# MCU.net
KiCad netlist of a schematic drawn in Altium Designer
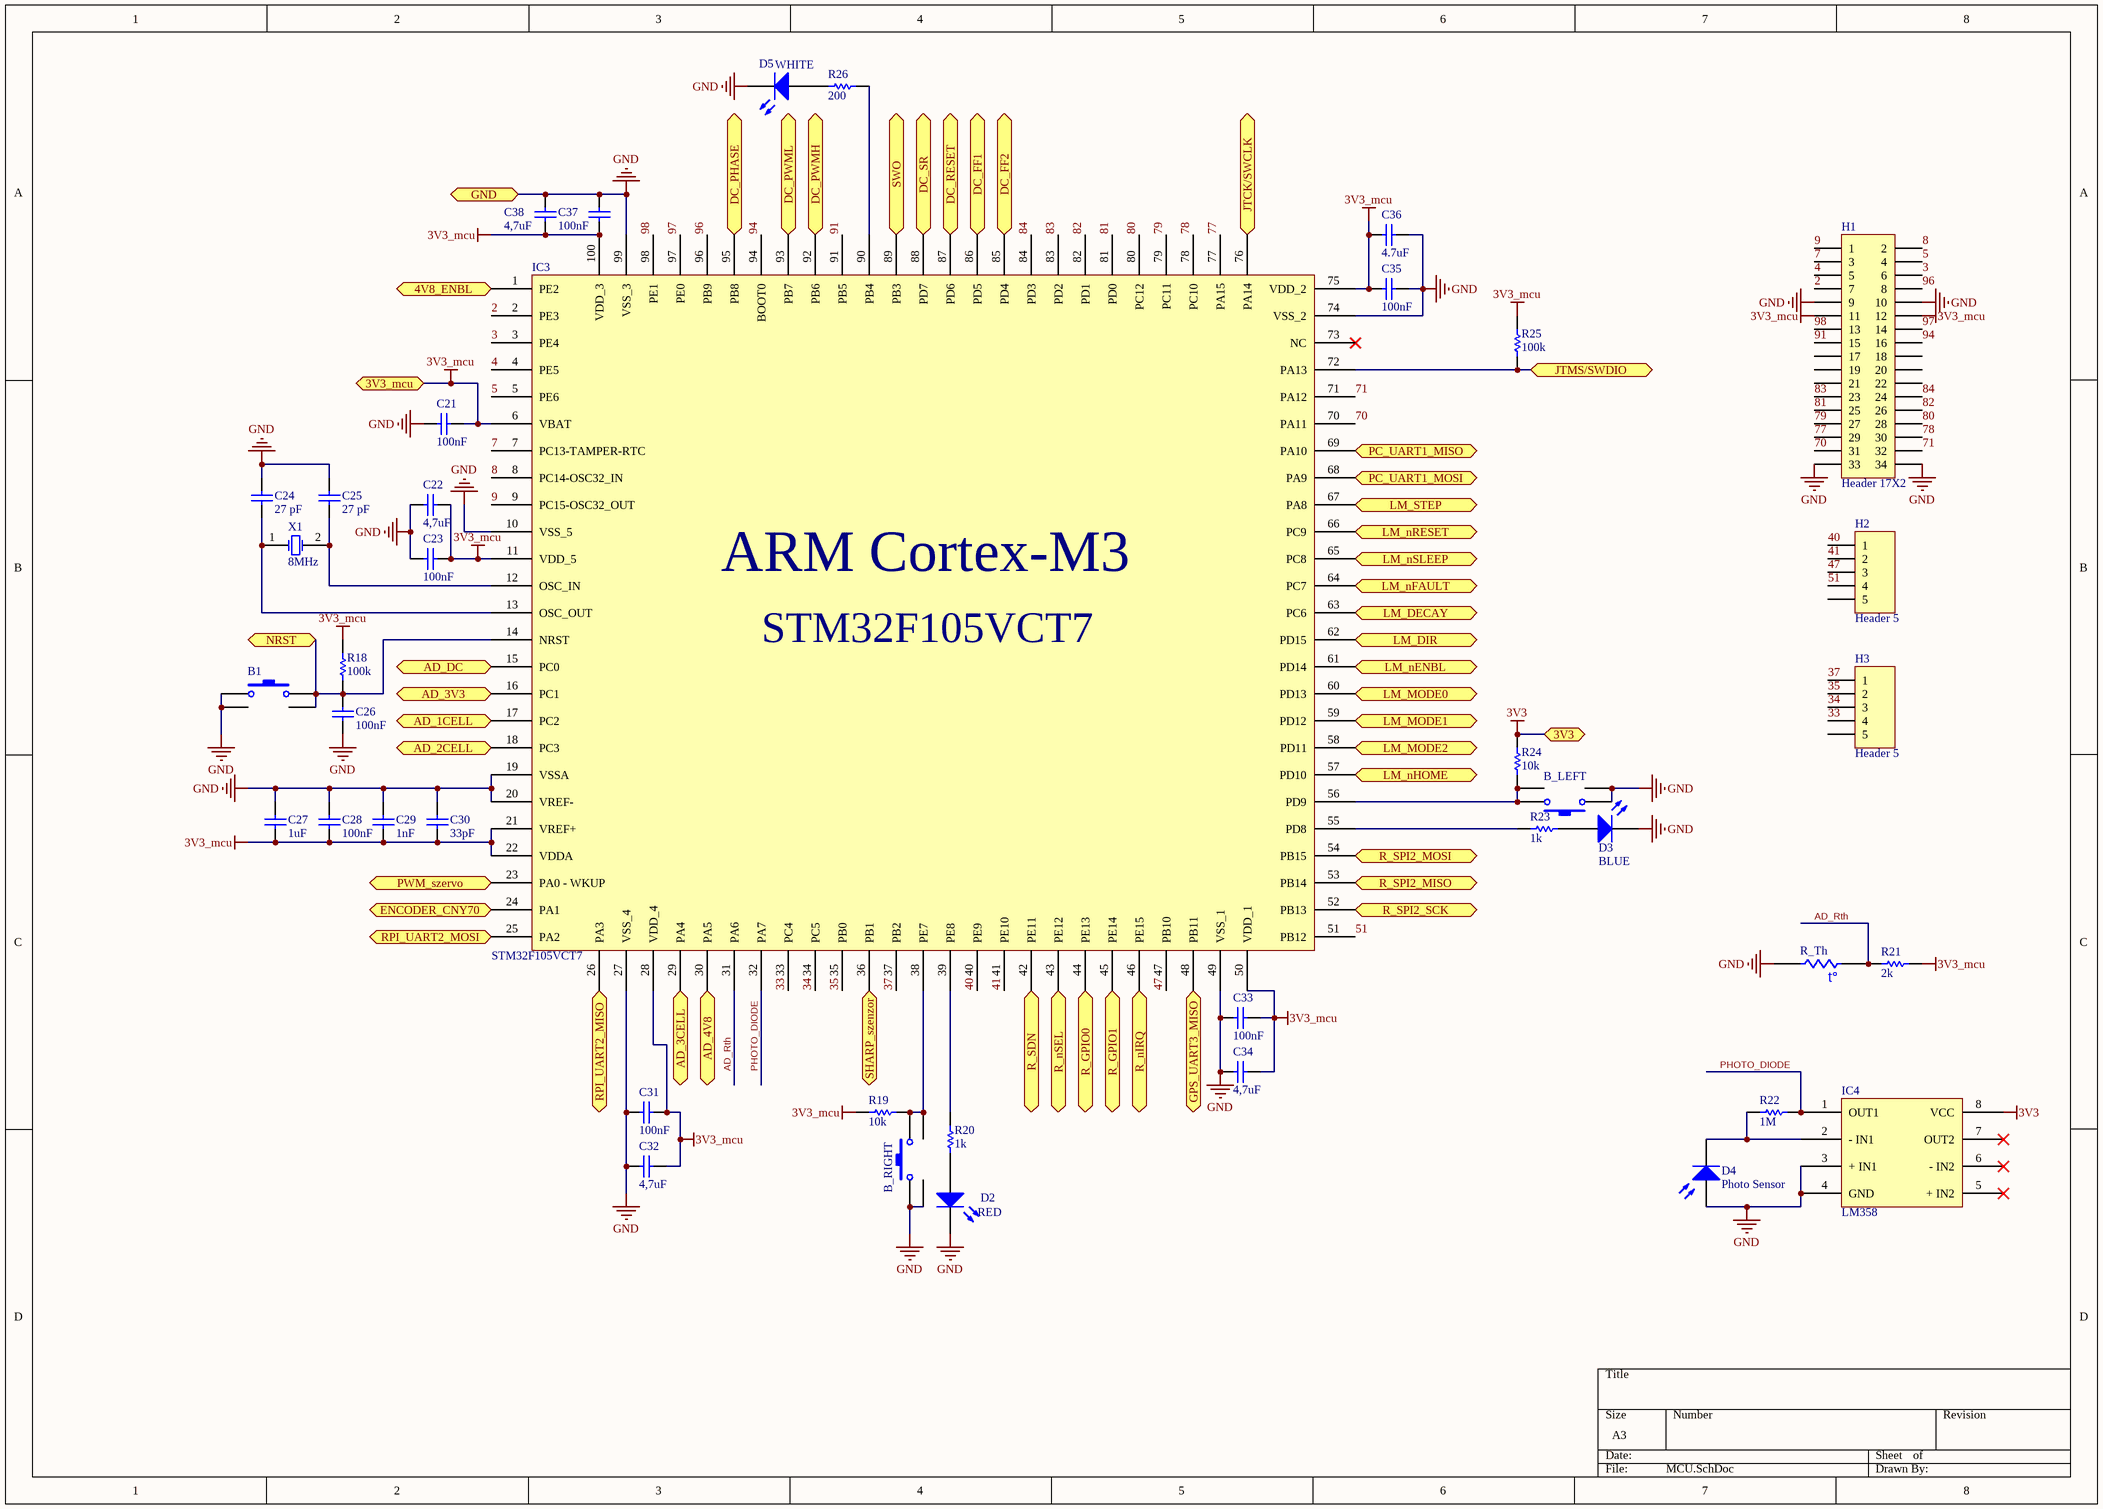
[diagram p0: MCU.SchDoc]

(export (version "E")
  (design (tool "Eeschema 10.0.6"))
  (components
    (comp (ref "B1")
      (value "SW-PB")
      (footprint "6x6 button")
      (description "Switch")
      (fields (field (name "PUBLISHER") "Altium Limited"))
      (libsource (lib "Miscellaneous Devices") (part "SW-PB"))
    )
    (comp (ref "B_LEFT")
      (value "SW-PB")
      (footprint "6x6 button")
      (description "Switch")
      (fields (field (name "PUBLISHER") "Altium Limited"))
      (libsource (lib "Miscellaneous Devices") (part "SW-PB"))
    )
    (comp (ref "B_RIGHT")
      (value "SW-PB")
      (footprint "6x6 button")
      (description "Switch")
      (fields (field (name "PUBLISHER") "Altium Limited"))
      (libsource (lib "Miscellaneous Devices") (part "SW-PB"))
    )
    (comp (ref "C21")
      (value "100nF")
      (footprint "FP_0603_CAP_080")
      (description "Capacitor")
      (fields (field (name "Comment") "Cap") (field (name "PUBLISHER") "Altium Limited"))
      (libsource (lib "Miscellaneous Devices") (part "Cap"))
    )
    (comp (ref "C22")
      (value "4,7uF")
      (footprint "FP_0603_CAP_080")
      (description "Capacitor")
      (fields (field (name "Comment") "Cap") (field (name "PUBLISHER") "Altium Limited"))
      (libsource (lib "Miscellaneous Devices") (part "Cap"))
    )
    (comp (ref "C23")
      (value "100nF")
      (footprint "FP_0603_CAP_080")
      (description "Capacitor")
      (fields (field (name "Comment") "Cap") (field (name "PUBLISHER") "Altium Limited"))
      (libsource (lib "Miscellaneous Devices") (part "Cap"))
    )
    (comp (ref "C24")
      (value "27 pF")
      (footprint "FP_0603_CAP_080")
      (description "Capacitor")
      (fields (field (name "Comment") "Cap") (field (name "PUBLISHER") "Altium Limited"))
      (libsource (lib "Miscellaneous Devices") (part "Cap"))
    )
    (comp (ref "C25")
      (value "27 pF")
      (footprint "FP_0603_CAP_080")
      (description "Capacitor")
      (fields (field (name "Comment") "Cap") (field (name "PUBLISHER") "Altium Limited"))
      (libsource (lib "Miscellaneous Devices") (part "Cap"))
    )
    (comp (ref "C26")
      (value "100nF")
      (footprint "FP_0603_CAP_080")
      (description "Capacitor")
      (fields (field (name "Comment") "Cap") (field (name "PUBLISHER") "Altium Limited"))
      (libsource (lib "Miscellaneous Devices") (part "Cap"))
    )
    (comp (ref "C27")
      (value "1uF")
      (footprint "FP_0603_CAP_080")
      (description "Capacitor")
      (fields (field (name "Comment") "Cap") (field (name "PUBLISHER") "Altium Limited"))
      (libsource (lib "Miscellaneous Devices") (part "Cap"))
    )
    (comp (ref "C28")
      (value "100nF")
      (footprint "FP_0603_CAP_080")
      (description "Capacitor")
      (fields (field (name "Comment") "Cap") (field (name "PUBLISHER") "Altium Limited"))
      (libsource (lib "Miscellaneous Devices") (part "Cap"))
    )
    (comp (ref "C29")
      (value "1nF")
      (footprint "FP_0603_CAP_080")
      (description "Capacitor")
      (fields (field (name "Comment") "Cap") (field (name "PUBLISHER") "Altium Limited"))
      (libsource (lib "Miscellaneous Devices") (part "Cap"))
    )
    (comp (ref "C30")
      (value "33pF")
      (footprint "FP_0603_CAP_080")
      (description "Capacitor")
      (fields (field (name "Comment") "Cap") (field (name "PUBLISHER") "Altium Limited"))
      (libsource (lib "Miscellaneous Devices") (part "Cap"))
    )
    (comp (ref "C31")
      (value "100nF")
      (footprint "FP_0603_CAP_080")
      (description "Capacitor")
      (fields (field (name "Comment") "Cap") (field (name "PUBLISHER") "Altium Limited"))
      (libsource (lib "Miscellaneous Devices") (part "Cap"))
    )
    (comp (ref "C32")
      (value "4,7uF")
      (footprint "FP_0603_CAP_080")
      (description "Capacitor")
      (fields (field (name "Comment") "Cap") (field (name "PUBLISHER") "Altium Limited"))
      (libsource (lib "Miscellaneous Devices") (part "Cap"))
    )
    (comp (ref "C33")
      (value "100nF")
      (footprint "FP_0603_CAP_080")
      (description "Capacitor")
      (fields (field (name "Comment") "Cap") (field (name "PUBLISHER") "Altium Limited"))
      (libsource (lib "Miscellaneous Devices") (part "Cap"))
    )
    (comp (ref "C34")
      (value "4,7uF")
      (footprint "FP_0603_CAP_080")
      (description "Capacitor")
      (fields (field (name "Comment") "Cap") (field (name "PUBLISHER") "Altium Limited"))
      (libsource (lib "Miscellaneous Devices") (part "Cap"))
    )
    (comp (ref "C35")
      (value "100nF")
      (footprint "FP_0603_CAP_080")
      (description "Capacitor")
      (fields (field (name "Comment") "Cap") (field (name "PUBLISHER") "Altium Limited"))
      (libsource (lib "Miscellaneous Devices") (part "Cap"))
    )
    (comp (ref "C36")
      (value "4.7uF")
      (footprint "FP_0603_CAP_080")
      (description "Capacitor")
      (fields (field (name "Comment") "Cap") (field (name "PUBLISHER") "Altium Limited"))
      (libsource (lib "Miscellaneous Devices") (part "Cap"))
    )
    (comp (ref "C37")
      (value "100nF")
      (footprint "FP_0603_CAP_080")
      (description "Capacitor")
      (fields (field (name "Comment") "Cap") (field (name "PUBLISHER") "Altium Limited"))
      (libsource (lib "Miscellaneous Devices") (part "Cap"))
    )
    (comp (ref "C38")
      (value "4,7uF")
      (footprint "FP_0603_CAP_080")
      (description "Capacitor")
      (fields (field (name "Comment") "Cap") (field (name "PUBLISHER") "Altium Limited"))
      (libsource (lib "Miscellaneous Devices") (part "Cap"))
    )
    (comp (ref "D2")
      (value "RED")
      (footprint "FP_1206_CAP_085")
      (description "Typical INFRARED GaAs LED")
      (fields (field (name "PUBLISHER") "Altium Limited"))
      (libsource (lib "Miscellaneous Devices") (part "LED0"))
    )
    (comp (ref "D3")
      (value "BLUE")
      (footprint "FP_1206_CAP_085")
      (description "Typical INFRARED GaAs LED")
      (fields (field (name "PUBLISHER") "Altium Limited"))
      (libsource (lib "Miscellaneous Devices") (part "LED0"))
    )
    (comp (ref "D4")
      (value "Photo Sensor")
      (footprint "FP_CONN2_TUSKE_254MM")
      (description "Photosensitive Diode")
      (fields (field (name "PUBLISHER") "Altium Limited"))
      (libsource (lib "Miscellaneous Devices") (part "Photo Sen"))
    )
    (comp (ref "D5")
      (value "WHITE")
      (footprint "FP_CONN2_TUSKE_254MM")
      (description "Typical INFRARED GaAs LED")
      (fields (field (name "PUBLISHER") "Altium Limited"))
      (libsource (lib "Miscellaneous Devices") (part "LED0"))
    )
    (comp (ref "H1")
      (value "Header 17X2")
      (footprint "HDR2X17")
      (description "Header, 17-Pin, Dual row")
      (fields (field (name "PUBLISHER") "Altium Limited"))
      (libsource (lib "Miscellaneous Connectors") (part "Header 17X2"))
    )
    (comp (ref "H2")
      (value "Header 5")
      (footprint "HDR1X5")
      (description "Header, 5-Pin")
      (fields (field (name "PUBLISHER") "Altium Limited"))
      (libsource (lib "Miscellaneous Connectors") (part "Header 5"))
    )
    (comp (ref "H3")
      (value "Header 5")
      (footprint "HDR1X5")
      (description "Header, 5-Pin")
      (fields (field (name "PUBLISHER") "Altium Limited"))
      (libsource (lib "Miscellaneous Connectors") (part "Header 5"))
    )
    (comp (ref "IC3") (value "STM32F105VCT7") (libsource (lib "diploma") (part "STM32F105xx")))
    (comp (ref "IC4") (value "LM358") (footprint "SO-8_M") (libsource (lib "diploma") (part "LM358")))
    (comp (ref "R18")
      (value "100k")
      (footprint "FP_0603_RES")
      (description "Semiconductor Resistor")
      (fields (field (name "Comment") "Res Semi") (field (name "PUBLISHER") "Altium Limited"))
      (libsource (lib "Miscellaneous Devices") (part "Res Semi"))
    )
    (comp (ref "R19")
      (value "10k")
      (footprint "FP_0603_RES")
      (description "Semiconductor Resistor")
      (fields (field (name "Comment") "Res Semi") (field (name "PUBLISHER") "Altium Limited"))
      (libsource (lib "Miscellaneous Devices") (part "Res Semi"))
    )
    (comp (ref "R20")
      (value "1k")
      (footprint "FP_0603_RES")
      (description "Resistor")
      (fields (field (name "Comment") "Res1") (field (name "PUBLISHER") "Altium Limited"))
      (libsource (lib "Miscellaneous Devices") (part "Res1"))
    )
    (comp (ref "R21")
      (value "2k")
      (footprint "FP_0603_RES")
      (description "Resistor")
      (fields (field (name "Comment") "Res1") (field (name "PUBLISHER") "Altium Limited"))
      (libsource (lib "Miscellaneous Devices") (part "Res1"))
    )
    (comp (ref "R22")
      (value "1M")
      (footprint "FP_0603_RES")
      (description "Resistor")
      (fields (field (name "Comment") "Res1") (field (name "PUBLISHER") "Altium Limited"))
      (libsource (lib "Miscellaneous Devices") (part "Res1"))
    )
    (comp (ref "R23")
      (value "1k")
      (footprint "FP_0603_RES")
      (description "Resistor")
      (fields (field (name "Comment") "Res1") (field (name "PUBLISHER") "Altium Limited"))
      (libsource (lib "Miscellaneous Devices") (part "Res1"))
    )
    (comp (ref "R24")
      (value "10k")
      (footprint "FP_0603_RES")
      (description "Semiconductor Resistor")
      (fields (field (name "Comment") "Res Semi") (field (name "PUBLISHER") "Altium Limited"))
      (libsource (lib "Miscellaneous Devices") (part "Res Semi"))
    )
    (comp (ref "R25")
      (value "100k")
      (footprint "FP_0603_RES")
      (description "Semiconductor Resistor")
      (fields (field (name "Comment") "Res Semi") (field (name "PUBLISHER") "Altium Limited"))
      (libsource (lib "Miscellaneous Devices") (part "Res Semi"))
    )
    (comp (ref "R26")
      (value "200")
      (footprint "FP_0603_RES")
      (description "Resistor")
      (fields (field (name "Comment") "Res1") (field (name "PUBLISHER") "Altium Limited"))
      (libsource (lib "Miscellaneous Devices") (part "Res1"))
    )
    (comp (ref "R_Th")
      (value "Res Thermal")
      (footprint "HDR1X3")
      (description "Thermistor")
      (fields (field (name "PUBLISHER") "Altium Limited"))
      (libsource (lib "Miscellaneous Devices") (part "Res Thermal"))
    )
    (comp (ref "X1")
      (value "8MHz")
      (footprint "crystal_furatszerelt")
      (description "Crystal Oscillator")
      (fields (field (name "PUBLISHER") "Altium Limited"))
      (libsource (lib "Miscellaneous Devices") (part "XTAL"))
    )
  )
  (nets
    (net (code "1") (name "/2") (class "Default")
      (node (ref "H1") (pin "7") (pinfunction "7_7") (pintype "passive"))
      (node (ref "IC3") (pin "2") (pinfunction "PE3_2") (pintype "passive"))
    )
    (net (code "2") (name "/3") (class "Default")
      (node (ref "H1") (pin "6") (pinfunction "6_6") (pintype "passive"))
      (node (ref "IC3") (pin "3") (pinfunction "PE4_3") (pintype "passive"))
    )
    (net (code "3") (name "/4") (class "Default")
      (node (ref "H1") (pin "5") (pinfunction "5_5") (pintype "passive"))
      (node (ref "IC3") (pin "4") (pinfunction "PE5_4") (pintype "passive"))
    )
    (net (code "4") (name "/4V8_ENBL") (class "Default")
      (node (ref "IC3") (pin "1") (pinfunction "PE2_1") (pintype "passive"))
    )
    (net (code "5") (name "/5") (class "Default")
      (node (ref "H1") (pin "4") (pinfunction "4_4") (pintype "passive"))
      (node (ref "IC3") (pin "5") (pinfunction "PE6_5") (pintype "passive"))
    )
    (net (code "6") (name "/7") (class "Default")
      (node (ref "H1") (pin "3") (pinfunction "3_3") (pintype "passive"))
      (node (ref "IC3") (pin "7") (pinfunction "PC13-TAMPER-RTC_7") (pintype "passive"))
    )
    (net (code "7") (name "/8") (class "Default")
      (node (ref "H1") (pin "2") (pinfunction "2_2") (pintype "passive"))
      (node (ref "IC3") (pin "8") (pinfunction "PC14-OSC32_IN_8") (pintype "passive"))
    )
    (net (code "8") (name "/9") (class "Default")
      (node (ref "H1") (pin "1") (pinfunction "1_1") (pintype "passive"))
      (node (ref "IC3") (pin "9") (pinfunction "PC15-OSC32_OUT_9") (pintype "passive"))
    )
    (net (code "9") (name "/33") (class "Default")
      (node (ref "H3") (pin "4") (pinfunction "4_4") (pintype "passive"))
      (node (ref "IC3") (pin "33") (pinfunction "PC4_33") (pintype "passive"))
    )
    (net (code "10") (name "/34") (class "Default")
      (node (ref "H3") (pin "3") (pinfunction "3_3") (pintype "passive"))
      (node (ref "IC3") (pin "34") (pinfunction "PC5_34") (pintype "passive"))
    )
    (net (code "11") (name "/35") (class "Default")
      (node (ref "H3") (pin "2") (pinfunction "2_2") (pintype "passive"))
      (node (ref "IC3") (pin "35") (pinfunction "PB0_35") (pintype "passive"))
    )
    (net (code "12") (name "/37") (class "Default")
      (node (ref "H3") (pin "1") (pinfunction "1_1") (pintype "passive"))
      (node (ref "IC3") (pin "37") (pinfunction "PB2_37") (pintype "passive"))
    )
    (net (code "13") (name "/40") (class "Default")
      (node (ref "H2") (pin "1") (pinfunction "1_1") (pintype "passive"))
      (node (ref "IC3") (pin "40") (pinfunction "PE9_40") (pintype "passive"))
    )
    (net (code "14") (name "/41") (class "Default")
      (node (ref "H2") (pin "2") (pinfunction "2_2") (pintype "passive"))
      (node (ref "IC3") (pin "41") (pinfunction "PE10_41") (pintype "passive"))
    )
    (net (code "15") (name "/47") (class "Default")
      (node (ref "H2") (pin "3") (pinfunction "3_3") (pintype "passive"))
      (node (ref "IC3") (pin "47") (pinfunction "PB10_47") (pintype "passive"))
    )
    (net (code "16") (name "/51") (class "Default")
      (node (ref "H2") (pin "4") (pinfunction "4_4") (pintype "passive"))
      (node (ref "IC3") (pin "51") (pinfunction "PB12_51") (pintype "passive"))
    )
    (net (code "17") (name "/70") (class "Default")
      (node (ref "H1") (pin "31") (pinfunction "31_31") (pintype "passive"))
      (node (ref "IC3") (pin "70") (pinfunction "PA11_70") (pintype "passive"))
    )
    (net (code "18") (name "/71") (class "Default")
      (node (ref "H1") (pin "32") (pinfunction "32_32") (pintype "passive"))
      (node (ref "IC3") (pin "71") (pinfunction "PA12_71") (pintype "passive"))
    )
    (net (code "19") (name "/77") (class "Default")
      (node (ref "H1") (pin "29") (pinfunction "29_29") (pintype "passive"))
      (node (ref "IC3") (pin "77") (pinfunction "PA15_77") (pintype "passive"))
    )
    (net (code "20") (name "/78") (class "Default")
      (node (ref "H1") (pin "30") (pinfunction "30_30") (pintype "passive"))
      (node (ref "IC3") (pin "78") (pinfunction "PC10_78") (pintype "passive"))
    )
    (net (code "21") (name "/79") (class "Default")
      (node (ref "H1") (pin "27") (pinfunction "27_27") (pintype "passive"))
      (node (ref "IC3") (pin "79") (pinfunction "PC11_79") (pintype "passive"))
    )
    (net (code "22") (name "/80") (class "Default")
      (node (ref "H1") (pin "28") (pinfunction "28_28") (pintype "passive"))
      (node (ref "IC3") (pin "80") (pinfunction "PC12_80") (pintype "passive"))
    )
    (net (code "23") (name "/81") (class "Default")
      (node (ref "H1") (pin "25") (pinfunction "25_25") (pintype "passive"))
      (node (ref "IC3") (pin "81") (pinfunction "PD0_81") (pintype "passive"))
    )
    (net (code "24") (name "/82") (class "Default")
      (node (ref "H1") (pin "26") (pinfunction "26_26") (pintype "passive"))
      (node (ref "IC3") (pin "82") (pinfunction "PD1_82") (pintype "passive"))
    )
    (net (code "25") (name "/83") (class "Default")
      (node (ref "H1") (pin "23") (pinfunction "23_23") (pintype "passive"))
      (node (ref "IC3") (pin "83") (pinfunction "PD2_83") (pintype "passive"))
    )
    (net (code "26") (name "/84") (class "Default")
      (node (ref "H1") (pin "24") (pinfunction "24_24") (pintype "passive"))
      (node (ref "IC3") (pin "84") (pinfunction "PD3_84") (pintype "passive"))
    )
    (net (code "27") (name "/91") (class "Default")
      (node (ref "H1") (pin "15") (pinfunction "15_15") (pintype "passive"))
      (node (ref "IC3") (pin "91") (pinfunction "PB5_91") (pintype "passive"))
    )
    (net (code "28") (name "/94") (class "Default")
      (node (ref "H1") (pin "16") (pinfunction "16_16") (pintype "passive"))
      (node (ref "IC3") (pin "94") (pinfunction "BOOT0_94") (pintype "passive"))
    )
    (net (code "29") (name "/96") (class "Default")
      (node (ref "H1") (pin "8") (pinfunction "8_8") (pintype "passive"))
      (node (ref "IC3") (pin "96") (pinfunction "PB9_96") (pintype "passive"))
    )
    (net (code "30") (name "/97") (class "Default")
      (node (ref "H1") (pin "14") (pinfunction "14_14") (pintype "passive"))
      (node (ref "IC3") (pin "97") (pinfunction "PE0_97") (pintype "passive"))
    )
    (net (code "31") (name "/98") (class "Default")
      (node (ref "H1") (pin "13") (pinfunction "13_13") (pintype "passive"))
      (node (ref "IC3") (pin "98") (pinfunction "PE1_98") (pintype "passive"))
    )
    (net (code "32") (name "/AD_1CELL") (class "Default")
      (node (ref "IC3") (pin "17") (pinfunction "PC2_17") (pintype "passive"))
    )
    (net (code "33") (name "/AD_2CELL") (class "Default")
      (node (ref "IC3") (pin "18") (pinfunction "PC3_18") (pintype "passive"))
    )
    (net (code "34") (name "/AD_3CELL") (class "Default")
      (node (ref "IC3") (pin "29") (pinfunction "PA4_29") (pintype "passive"))
    )
    (net (code "35") (name "/AD_3V3") (class "Default")
      (node (ref "IC3") (pin "16") (pinfunction "PC1_16") (pintype "passive"))
    )
    (net (code "36") (name "/AD_4V8") (class "Default")
      (node (ref "IC3") (pin "30") (pinfunction "PA5_30") (pintype "passive"))
    )
    (net (code "37") (name "/AD_DC") (class "Default")
      (node (ref "IC3") (pin "15") (pinfunction "PC0_15") (pintype "passive"))
    )
    (net (code "38") (name "/AD_Rth") (class "Default")
      (node (ref "IC3") (pin "31") (pinfunction "PA6_31") (pintype "passive"))
      (node (ref "R21") (pin "2") (pinfunction "2_2") (pintype "passive"))
      (node (ref "R_Th") (pin "1") (pinfunction "1_1") (pintype "passive"))
    )
    (net (code "39") (name "/DC_FF1") (class "Default")
      (node (ref "IC3") (pin "86") (pinfunction "PD5_86") (pintype "passive"))
    )
    (net (code "40") (name "/DC_FF2") (class "Default")
      (node (ref "IC3") (pin "85") (pinfunction "PD4_85") (pintype "passive"))
    )
    (net (code "41") (name "/DC_PHASE") (class "Default")
      (node (ref "IC3") (pin "95") (pinfunction "PB8_95") (pintype "passive"))
    )
    (net (code "42") (name "/DC_PWMH") (class "Default")
      (node (ref "IC3") (pin "92") (pinfunction "PB6_92") (pintype "passive"))
    )
    (net (code "43") (name "/DC_PWML") (class "Default")
      (node (ref "IC3") (pin "93") (pinfunction "PB7_93") (pintype "passive"))
    )
    (net (code "44") (name "/DC_RESET") (class "Default")
      (node (ref "IC3") (pin "87") (pinfunction "PD6_87") (pintype "passive"))
    )
    (net (code "45") (name "/DC_SR") (class "Default")
      (node (ref "IC3") (pin "88") (pinfunction "PD7_88") (pintype "passive"))
    )
    (net (code "46") (name "/ENCODER_CNY70") (class "Default")
      (node (ref "IC3") (pin "24") (pinfunction "PA1_24") (pintype "passive"))
    )
    (net (code "47") (name "/GPS_UART3_MISO") (class "Default")
      (node (ref "IC3") (pin "48") (pinfunction "PB11_48") (pintype "passive"))
    )
    (net (code "48") (name "/JTCK{slash}SWCLK") (class "Default")
      (node (ref "IC3") (pin "76") (pinfunction "PA14_76") (pintype "passive"))
    )
    (net (code "49") (name "/JTMS{slash}SWDIO") (class "Default")
      (node (ref "IC3") (pin "72") (pinfunction "PA13_72") (pintype "passive"))
      (node (ref "R25") (pin "1") (pinfunction "1_1") (pintype "passive"))
    )
    (net (code "50") (name "/LM_DECAY") (class "Default")
      (node (ref "IC3") (pin "63") (pinfunction "PC6_63") (pintype "passive"))
    )
    (net (code "51") (name "/LM_DIR") (class "Default")
      (node (ref "IC3") (pin "62") (pinfunction "PD15_62") (pintype "passive"))
    )
    (net (code "52") (name "/LM_MODE0") (class "Default")
      (node (ref "IC3") (pin "60") (pinfunction "PD13_60") (pintype "passive"))
    )
    (net (code "53") (name "/LM_MODE1") (class "Default")
      (node (ref "IC3") (pin "59") (pinfunction "PD12_59") (pintype "passive"))
    )
    (net (code "54") (name "/LM_MODE2") (class "Default")
      (node (ref "IC3") (pin "58") (pinfunction "PD11_58") (pintype "passive"))
    )
    (net (code "55") (name "/LM_STEP") (class "Default")
      (node (ref "IC3") (pin "67") (pinfunction "PA8_67") (pintype "passive"))
    )
    (net (code "56") (name "/LM_nENBL") (class "Default")
      (node (ref "IC3") (pin "61") (pinfunction "PD14_61") (pintype "passive"))
    )
    (net (code "57") (name "/LM_nFAULT") (class "Default")
      (node (ref "IC3") (pin "64") (pinfunction "PC7_64") (pintype "passive"))
    )
    (net (code "58") (name "/LM_nHOME") (class "Default")
      (node (ref "IC3") (pin "57") (pinfunction "PD10_57") (pintype "passive"))
    )
    (net (code "59") (name "/LM_nRESET") (class "Default")
      (node (ref "IC3") (pin "66") (pinfunction "PC9_66") (pintype "passive"))
    )
    (net (code "60") (name "/LM_nSLEEP") (class "Default")
      (node (ref "IC3") (pin "65") (pinfunction "PC8_65") (pintype "passive"))
    )
    (net (code "61") (name "/NRST") (class "Default")
      (node (ref "B1") (pin "2") (pinfunction "2_2") (pintype "passive"))
      (node (ref "C26") (pin "2") (pinfunction "2_2") (pintype "passive"))
      (node (ref "IC3") (pin "14") (pinfunction "NRST_14") (pintype "passive"))
      (node (ref "R18") (pin "2") (pinfunction "2_2") (pintype "passive"))
    )
    (net (code "62") (name "/PC_UART1_MISO") (class "Default")
      (node (ref "IC3") (pin "69") (pinfunction "PA10_69") (pintype "passive"))
    )
    (net (code "63") (name "/PC_UART1_MOSI") (class "Default")
      (node (ref "IC3") (pin "68") (pinfunction "PA9_68") (pintype "passive"))
    )
    (net (code "64") (name "/PHOTO_DIODE") (class "Default")
      (node (ref "IC3") (pin "32") (pinfunction "PA7_32") (pintype "passive"))
      (node (ref "IC4") (pin "1") (pinfunction "OUT1_1") (pintype "passive"))
      (node (ref "R22") (pin "2") (pinfunction "2_2") (pintype "passive"))
    )
    (net (code "65") (name "/PWM_szervo") (class "Default")
      (node (ref "IC3") (pin "23") (pinfunction "PA0_-_WKUP_23") (pintype "passive"))
    )
    (net (code "66") (name "/RPI_UART2_MISO") (class "Default")
      (node (ref "IC3") (pin "26") (pinfunction "PA3_26") (pintype "passive"))
    )
    (net (code "67") (name "/RPI_UART2_MOSI") (class "Default")
      (node (ref "IC3") (pin "25") (pinfunction "PA2_25") (pintype "passive"))
    )
    (net (code "68") (name "/R_GPIO0") (class "Default")
      (node (ref "IC3") (pin "44") (pinfunction "PE13_44") (pintype "passive"))
    )
    (net (code "69") (name "/R_GPIO1") (class "Default")
      (node (ref "IC3") (pin "45") (pinfunction "PE14_45") (pintype "passive"))
    )
    (net (code "70") (name "/R_SDN") (class "Default")
      (node (ref "IC3") (pin "42") (pinfunction "PE11_42") (pintype "passive"))
    )
    (net (code "71") (name "/R_SPI2_MISO") (class "Default")
      (node (ref "IC3") (pin "53") (pinfunction "PB14_53") (pintype "passive"))
    )
    (net (code "72") (name "/R_SPI2_MOSI") (class "Default")
      (node (ref "IC3") (pin "54") (pinfunction "PB15_54") (pintype "passive"))
    )
    (net (code "73") (name "/R_SPI2_SCK") (class "Default")
      (node (ref "IC3") (pin "52") (pinfunction "PB13_52") (pintype "passive"))
    )
    (net (code "74") (name "/R_nIRQ") (class "Default")
      (node (ref "IC3") (pin "46") (pinfunction "PE15_46") (pintype "passive"))
    )
    (net (code "75") (name "/R_nSEL") (class "Default")
      (node (ref "IC3") (pin "43") (pinfunction "PE12_43") (pintype "passive"))
    )
    (net (code "76") (name "/SHARP_szenzor") (class "Default")
      (node (ref "IC3") (pin "36") (pinfunction "PB1_36") (pintype "passive"))
    )
    (net (code "77") (name "/SWO") (class "Default")
      (node (ref "IC3") (pin "89") (pinfunction "PB3_89") (pintype "passive"))
    )
    (net (code "78") (name "3V3") (class "Default")
      (node (ref "IC4") (pin "8") (pinfunction "VCC_8") (pintype "passive"))
      (node (ref "R24") (pin "1") (pinfunction "1_1") (pintype "passive"))
    )
    (net (code "79") (name "3V3_mcu") (class "Default")
      (node (ref "C21") (pin "1") (pinfunction "1_1") (pintype "passive"))
      (node (ref "C22") (pin "1") (pinfunction "1_1") (pintype "passive"))
      (node (ref "C23") (pin "1") (pinfunction "1_1") (pintype "passive"))
      (node (ref "C27") (pin "2") (pinfunction "2_2") (pintype "passive"))
      (node (ref "C28") (pin "2") (pinfunction "2_2") (pintype "passive"))
      (node (ref "C29") (pin "2") (pinfunction "2_2") (pintype "passive"))
      (node (ref "C30") (pin "2") (pinfunction "2_2") (pintype "passive"))
      (node (ref "C31") (pin "1") (pinfunction "1_1") (pintype "passive"))
      (node (ref "C32") (pin "1") (pinfunction "1_1") (pintype "passive"))
      (node (ref "C33") (pin "1") (pinfunction "1_1") (pintype "passive"))
      (node (ref "C34") (pin "1") (pinfunction "1_1") (pintype "passive"))
      (node (ref "C35") (pin "1") (pinfunction "1_1") (pintype "passive"))
      (node (ref "C36") (pin "1") (pinfunction "1_1") (pintype "passive"))
      (node (ref "C37") (pin "1") (pinfunction "1_1") (pintype "passive"))
      (node (ref "C38") (pin "2") (pinfunction "2_2") (pintype "passive"))
      (node (ref "H1") (pin "11") (pinfunction "11_11") (pintype "passive"))
      (node (ref "H1") (pin "12") (pinfunction "12_12") (pintype "passive"))
      (node (ref "IC3") (pin "100") (pinfunction "VDD_3_100") (pintype "passive"))
      (node (ref "IC3") (pin "11") (pinfunction "VDD_5_11") (pintype "passive"))
      (node (ref "IC3") (pin "21") (pinfunction "VREF+_21") (pintype "passive"))
      (node (ref "IC3") (pin "22") (pinfunction "VDDA_22") (pintype "passive"))
      (node (ref "IC3") (pin "28") (pinfunction "VDD_4_28") (pintype "passive"))
      (node (ref "IC3") (pin "50") (pinfunction "VDD_1_50") (pintype "passive"))
      (node (ref "IC3") (pin "6") (pinfunction "VBAT_6") (pintype "passive"))
      (node (ref "IC3") (pin "75") (pinfunction "VDD_2_75") (pintype "passive"))
      (node (ref "R18") (pin "1") (pinfunction "1_1") (pintype "passive"))
      (node (ref "R19") (pin "2") (pinfunction "2_2") (pintype "passive"))
      (node (ref "R21") (pin "1") (pinfunction "1_1") (pintype "passive"))
      (node (ref "R25") (pin "2") (pinfunction "2_2") (pintype "passive"))
    )
    (net (code "80") (name "GND") (class "Default")
      (node (ref "B1") (pin "1") (pinfunction "1_1") (pintype "passive"))
      (node (ref "B_LEFT") (pin "1") (pinfunction "1_1") (pintype "passive"))
      (node (ref "B_RIGHT") (pin "1") (pinfunction "1_1") (pintype "passive"))
      (node (ref "C21") (pin "2") (pinfunction "2_2") (pintype "passive"))
      (node (ref "C22") (pin "2") (pinfunction "2_2") (pintype "passive"))
      (node (ref "C23") (pin "2") (pinfunction "2_2") (pintype "passive"))
      (node (ref "C24") (pin "1") (pinfunction "1_1") (pintype "passive"))
      (node (ref "C25") (pin "1") (pinfunction "1_1") (pintype "passive"))
      (node (ref "C26") (pin "1") (pinfunction "1_1") (pintype "passive"))
      (node (ref "C27") (pin "1") (pinfunction "1_1") (pintype "passive"))
      (node (ref "C28") (pin "1") (pinfunction "1_1") (pintype "passive"))
      (node (ref "C29") (pin "1") (pinfunction "1_1") (pintype "passive"))
      (node (ref "C30") (pin "1") (pinfunction "1_1") (pintype "passive"))
      (node (ref "C31") (pin "2") (pinfunction "2_2") (pintype "passive"))
      (node (ref "C32") (pin "2") (pinfunction "2_2") (pintype "passive"))
      (node (ref "C33") (pin "2") (pinfunction "2_2") (pintype "passive"))
      (node (ref "C34") (pin "2") (pinfunction "2_2") (pintype "passive"))
      (node (ref "C35") (pin "2") (pinfunction "2_2") (pintype "passive"))
      (node (ref "C36") (pin "2") (pinfunction "2_2") (pintype "passive"))
      (node (ref "C37") (pin "2") (pinfunction "2_2") (pintype "passive"))
      (node (ref "C38") (pin "1") (pinfunction "1_1") (pintype "passive"))
      (node (ref "D2") (pin "2") (pinfunction "K_2") (pintype "passive"))
      (node (ref "D3") (pin "2") (pinfunction "K_2") (pintype "passive"))
      (node (ref "D4") (pin "1") (pinfunction "A_1") (pintype "passive"))
      (node (ref "D5") (pin "2") (pinfunction "K_2") (pintype "passive"))
      (node (ref "H1") (pin "10") (pinfunction "10_10") (pintype "passive"))
      (node (ref "H1") (pin "33") (pinfunction "33_33") (pintype "passive"))
      (node (ref "H1") (pin "34") (pinfunction "34_34") (pintype "passive"))
      (node (ref "H1") (pin "9") (pinfunction "9_9") (pintype "passive"))
      (node (ref "IC3") (pin "10") (pinfunction "VSS_5_10") (pintype "passive"))
      (node (ref "IC3") (pin "19") (pinfunction "VSSA_19") (pintype "passive"))
      (node (ref "IC3") (pin "20") (pinfunction "VREF-_20") (pintype "passive"))
      (node (ref "IC3") (pin "27") (pinfunction "VSS_4_27") (pintype "passive"))
      (node (ref "IC3") (pin "49") (pinfunction "VSS_1_49") (pintype "passive"))
      (node (ref "IC3") (pin "74") (pinfunction "VSS_2_74") (pintype "passive"))
      (node (ref "IC3") (pin "99") (pinfunction "VSS_3_99") (pintype "passive"))
      (node (ref "IC4") (pin "3") (pinfunction "+_IN1_3") (pintype "passive"))
      (node (ref "IC4") (pin "4") (pinfunction "GND_4") (pintype "passive"))
      (node (ref "R_Th") (pin "3") (pinfunction "3_3") (pintype "passive"))
    )
    (net (code "81") (name "Net-(D2-A)") (class "Default")
      (node (ref "D2") (pin "1") (pinfunction "A_1") (pintype "passive"))
      (node (ref "R20") (pin "2") (pinfunction "2_2") (pintype "passive"))
    )
    (net (code "82") (name "Net-(D3-A)") (class "Default")
      (node (ref "D3") (pin "1") (pinfunction "A_1") (pintype "passive"))
      (node (ref "R23") (pin "1") (pinfunction "1_1") (pintype "passive"))
    )
    (net (code "83") (name "Net-(D4-K)") (class "Default")
      (node (ref "D4") (pin "2") (pinfunction "K_2") (pintype "passive"))
      (node (ref "IC4") (pin "2") (pinfunction "-_IN1_2") (pintype "passive"))
      (node (ref "R22") (pin "1") (pinfunction "1_1") (pintype "passive"))
    )
    (net (code "84") (name "Net-(D5-A)") (class "Default")
      (node (ref "D5") (pin "1") (pinfunction "A_1") (pintype "passive"))
      (node (ref "R26") (pin "1") (pinfunction "1_1") (pintype "passive"))
    )
    (net (code "85") (name "Net-(IC3-OSC_IN)") (class "Default")
      (node (ref "C25") (pin "2") (pinfunction "2_2") (pintype "passive"))
      (node (ref "IC3") (pin "12") (pinfunction "OSC_IN_12") (pintype "passive"))
      (node (ref "X1") (pin "2") (pinfunction "OSC2_2") (pintype "passive"))
    )
    (net (code "86") (name "Net-(IC3-OSC_OUT)") (class "Default")
      (node (ref "C24") (pin "2") (pinfunction "2_2") (pintype "passive"))
      (node (ref "IC3") (pin "13") (pinfunction "OSC_OUT_13") (pintype "passive"))
      (node (ref "X1") (pin "1") (pinfunction "OSC1_1") (pintype "passive"))
    )
    (net (code "87") (name "Net-(IC3-PB4)") (class "Default")
      (node (ref "IC3") (pin "90") (pinfunction "PB4_90") (pintype "passive"))
      (node (ref "R26") (pin "2") (pinfunction "2_2") (pintype "passive"))
    )
    (net (code "88") (name "Net-(IC3-PD8)") (class "Default")
      (node (ref "IC3") (pin "55") (pinfunction "PD8_55") (pintype "passive"))
      (node (ref "R23") (pin "2") (pinfunction "2_2") (pintype "passive"))
    )
    (net (code "89") (name "Net-(IC3-PD9)") (class "Default")
      (node (ref "B_LEFT") (pin "2") (pinfunction "2_2") (pintype "passive"))
      (node (ref "IC3") (pin "56") (pinfunction "PD9_56") (pintype "passive"))
      (node (ref "R24") (pin "2") (pinfunction "2_2") (pintype "passive"))
    )
    (net (code "90") (name "Net-(IC3-PE7)") (class "Default")
      (node (ref "B_RIGHT") (pin "2") (pinfunction "2_2") (pintype "passive"))
      (node (ref "IC3") (pin "38") (pinfunction "PE7_38") (pintype "passive"))
      (node (ref "R19") (pin "1") (pinfunction "1_1") (pintype "passive"))
    )
    (net (code "91") (name "Net-(IC3-PE8)") (class "Default")
      (node (ref "IC3") (pin "39") (pinfunction "PE8_39") (pintype "passive"))
      (node (ref "R20") (pin "1") (pinfunction "1_1") (pintype "passive"))
    )
    (net (code "92") (name "unconnected-(H1-Pad17)") (class "Default")
      (node (ref "H1") (pin "17") (pinfunction "17_17") (pintype "passive"))
    )
    (net (code "93") (name "unconnected-(H1-Pad18)") (class "Default")
      (node (ref "H1") (pin "18") (pinfunction "18_18") (pintype "passive"))
    )
    (net (code "94") (name "unconnected-(H1-Pad19)") (class "Default")
      (node (ref "H1") (pin "19") (pinfunction "19_19") (pintype "passive"))
    )
    (net (code "95") (name "unconnected-(H1-Pad20)") (class "Default")
      (node (ref "H1") (pin "20") (pinfunction "20_20") (pintype "passive"))
    )
    (net (code "96") (name "unconnected-(H1-Pad21)") (class "Default")
      (node (ref "H1") (pin "21") (pinfunction "21_21") (pintype "passive"))
    )
    (net (code "97") (name "unconnected-(H1-Pad22)") (class "Default")
      (node (ref "H1") (pin "22") (pinfunction "22_22") (pintype "passive"))
    )
    (net (code "98") (name "unconnected-(H2-Pad5)") (class "Default")
      (node (ref "H2") (pin "5") (pinfunction "5_5") (pintype "passive"))
    )
    (net (code "99") (name "unconnected-(H3-Pad5)") (class "Default")
      (node (ref "H3") (pin "5") (pinfunction "5_5") (pintype "passive"))
    )
    (net (code "100") (name "unconnected-(IC3-NC-Pad73)") (class "Default")
      (node (ref "IC3") (pin "73") (pinfunction "NC_73") (pintype "passive+no_connect"))
    )
    (net (code "101") (name "unconnected-(IC4-+_IN2-Pad5)") (class "Default")
      (node (ref "IC4") (pin "5") (pinfunction "+_IN2_5") (pintype "passive+no_connect"))
    )
    (net (code "102") (name "unconnected-(IC4--_IN2-Pad6)") (class "Default")
      (node (ref "IC4") (pin "6") (pinfunction "-_IN2_6") (pintype "passive+no_connect"))
    )
    (net (code "103") (name "unconnected-(IC4-OUT2-Pad7)") (class "Default")
      (node (ref "IC4") (pin "7") (pinfunction "OUT2_7") (pintype "passive+no_connect"))
    )
  )
)
